# rauschsimulator_V4.net
KiCad netlist of a schematic drawn in EAGLE
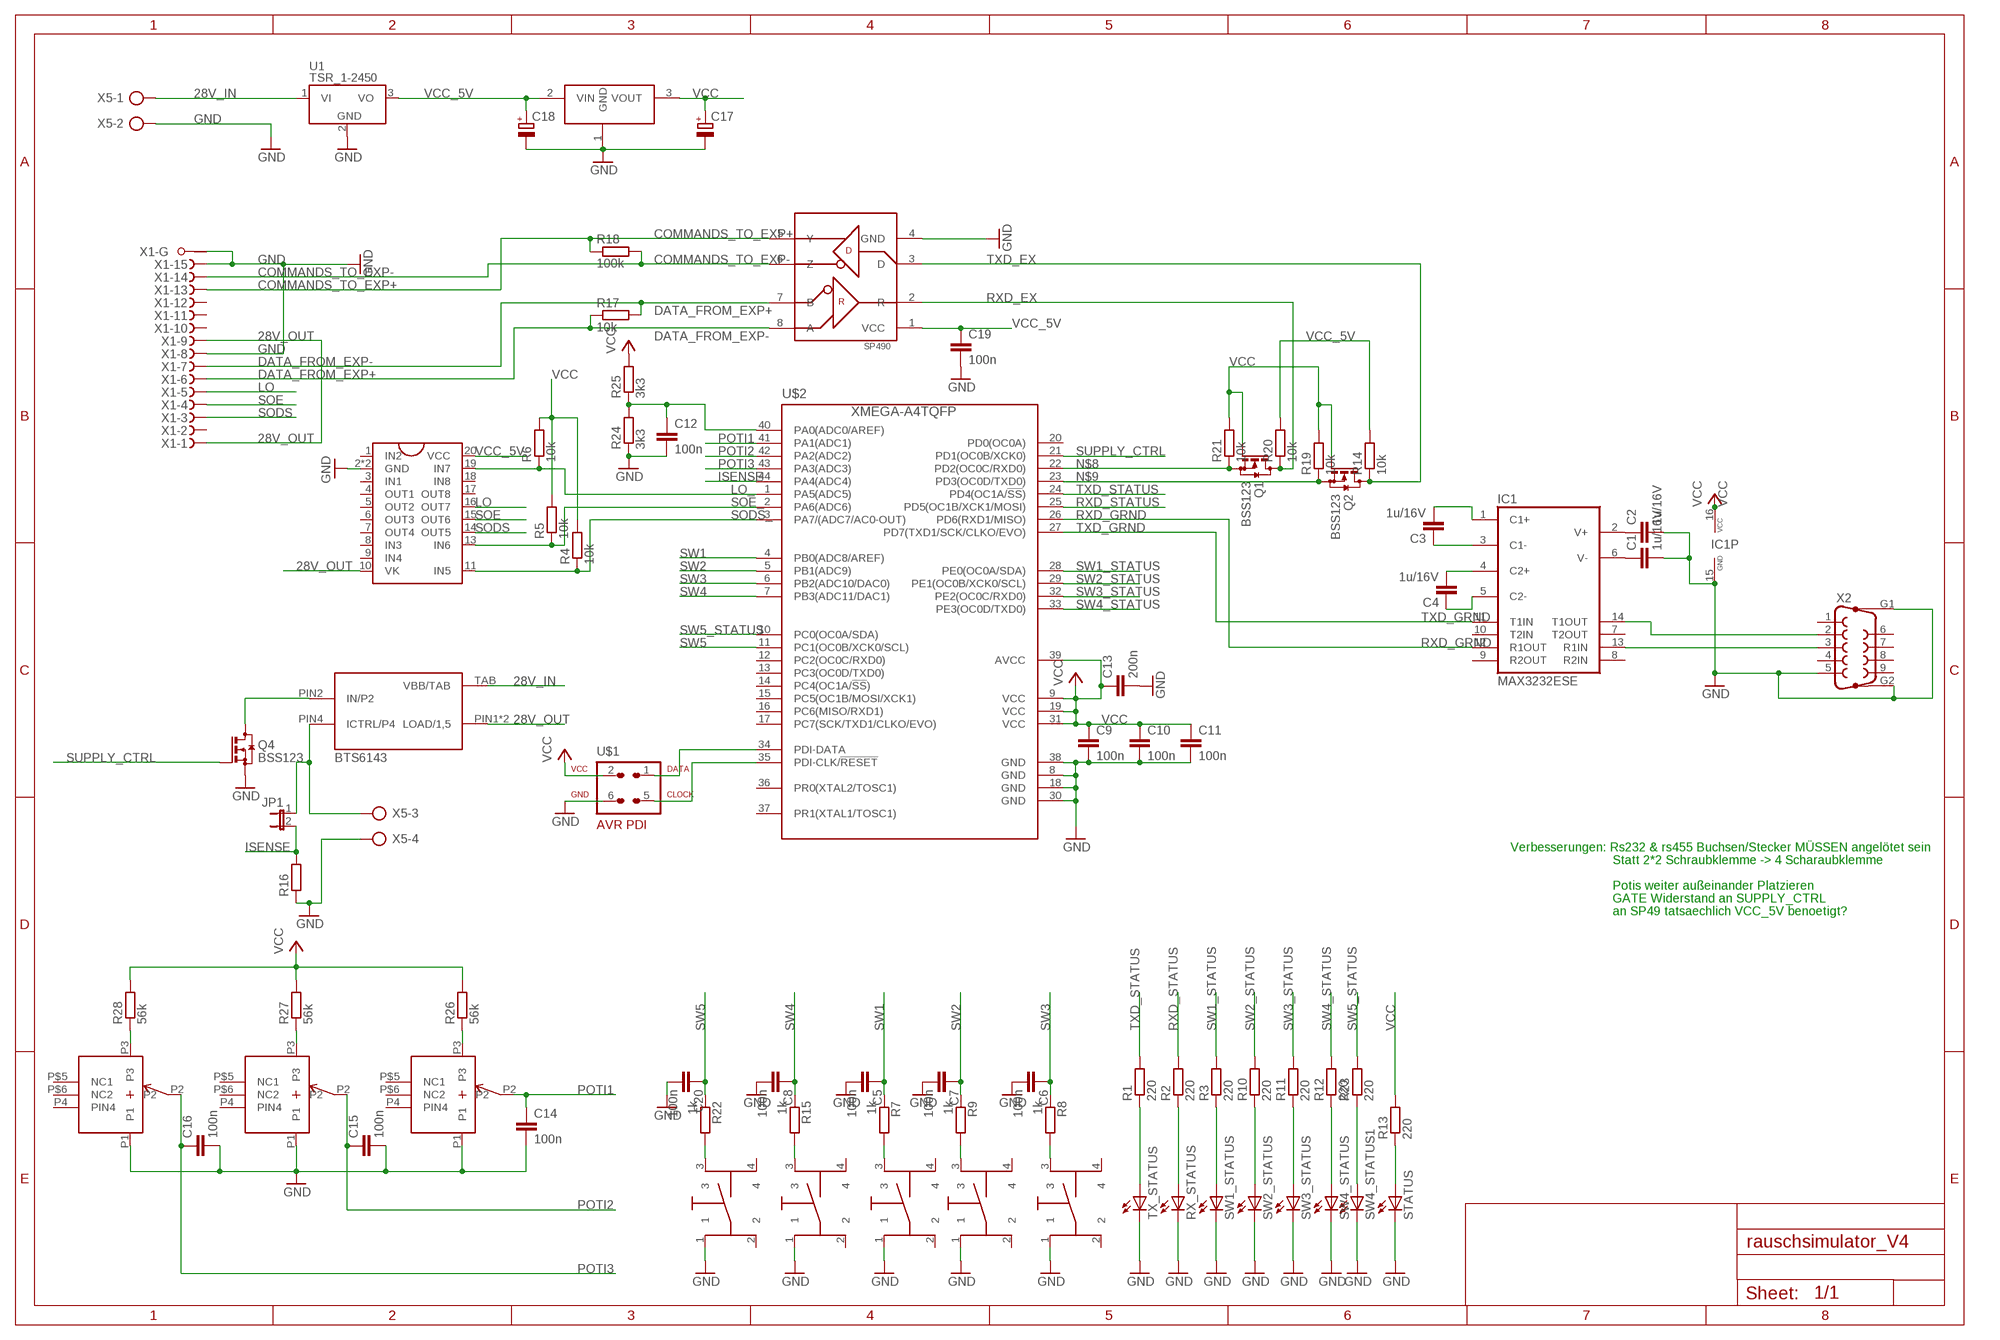
[diagram p0: schematic, sheet 1]

(export (version "E")
  (design (tool "Eeschema 10.0.6"))
  (components
    (comp (ref "C1")
      (value "1u/16V")
      (footprint "eagle-import:C0603K")
      (libsource (lib "eagle-import") (part "C-EUC0603K"))
    )
    (comp (ref "C2")
      (value "1u/16V")
      (footprint "eagle-import:C0603K")
      (libsource (lib "eagle-import") (part "C-EUC0603K"))
    )
    (comp (ref "C3")
      (value "1u/16V")
      (footprint "eagle-import:C0603K")
      (libsource (lib "eagle-import") (part "C-EUC0603K"))
    )
    (comp (ref "C4")
      (value "1u/16V")
      (footprint "eagle-import:C0603K")
      (libsource (lib "eagle-import") (part "C-EUC0603K"))
    )
    (comp (ref "C5")
      (value "100n")
      (footprint "eagle-import:C0603K")
      (libsource (lib "eagle-import") (part "C-EUC0603K"))
    )
    (comp (ref "C6")
      (value "100n")
      (footprint "eagle-import:C0603K")
      (libsource (lib "eagle-import") (part "C-EUC0603K"))
    )
    (comp (ref "C7")
      (value "100n")
      (footprint "eagle-import:C0603K")
      (libsource (lib "eagle-import") (part "C-EUC0603K"))
    )
    (comp (ref "C8")
      (value "100n")
      (footprint "eagle-import:C0603K")
      (libsource (lib "eagle-import") (part "C-EUC0603K"))
    )
    (comp (ref "C9")
      (value "100n")
      (footprint "eagle-import:C0603K")
      (libsource (lib "eagle-import") (part "C-EUC0603K"))
    )
    (comp (ref "C10")
      (value "100n")
      (footprint "eagle-import:C0603K")
      (libsource (lib "eagle-import") (part "C-EUC0603K"))
    )
    (comp (ref "C11")
      (value "100n")
      (footprint "eagle-import:C0603K")
      (libsource (lib "eagle-import") (part "C-EUC0603K"))
    )
    (comp (ref "C12")
      (value "100n")
      (footprint "eagle-import:C0603K")
      (libsource (lib "eagle-import") (part "C-EUC0603K"))
    )
    (comp (ref "C13")
      (value "200n")
      (footprint "eagle-import:C0603K")
      (libsource (lib "eagle-import") (part "C-EUC0603K"))
    )
    (comp (ref "C14")
      (value "100n")
      (footprint "eagle-import:C0603K")
      (libsource (lib "eagle-import") (part "C-EUC0603K"))
    )
    (comp (ref "C15")
      (value "100n")
      (footprint "eagle-import:C0603K")
      (libsource (lib "eagle-import") (part "C-EUC0603K"))
    )
    (comp (ref "C16")
      (value "100n")
      (footprint "eagle-import:C0603K")
      (libsource (lib "eagle-import") (part "C-EUC0603K"))
    )
    (comp (ref "C17")
      (value "CPOL-EUE2.5-6")
      (footprint "eagle-import:E2,5-6")
      (libsource (lib "eagle-import") (part "CPOL-EUE2.5-6"))
    )
    (comp (ref "C18")
      (value "CPOL-EUE2.5-6")
      (footprint "eagle-import:E2,5-6")
      (libsource (lib "eagle-import") (part "CPOL-EUE2.5-6"))
    )
    (comp (ref "C19")
      (value "100n")
      (footprint "eagle-import:C0603K")
      (libsource (lib "eagle-import") (part "C-EUC0603K"))
    )
    (comp (ref "C20")
      (value "100n")
      (footprint "eagle-import:C0603K")
      (libsource (lib "eagle-import") (part "C-EUC0603K"))
    )
    (comp (ref "IC1")
      (value "MAX3232ESE")
      (footprint "eagle-import:SO16")
      (fields (field (name "MF") "MAXIM"))
      (libsource (lib "eagle-import") (part "MAX3232SEE"))
    )
    (comp (ref "JP1")
      (value "JP1E")
      (footprint "eagle-import:JP1")
      (libsource (lib "eagle-import") (part "JP1E"))
    )
    (comp (ref "Q1")
      (value "BSS123")
      (footprint "eagle-import:SOT23")
      (libsource (lib "eagle-import") (part "BSS123"))
    )
    (comp (ref "Q2")
      (value "BSS123")
      (footprint "eagle-import:SOT23")
      (libsource (lib "eagle-import") (part "BSS123"))
    )
    (comp (ref "Q4")
      (value "BSS123")
      (footprint "eagle-import:SOT23")
      (libsource (lib "eagle-import") (part "BSS123"))
    )
    (comp (ref "R1")
      (value "220")
      (footprint "eagle-import:R0603")
      (libsource (lib "eagle-import") (part "R-EU_R0603"))
    )
    (comp (ref "R2")
      (value "220")
      (footprint "eagle-import:R0603")
      (libsource (lib "eagle-import") (part "R-EU_R0603"))
    )
    (comp (ref "R3")
      (value "220")
      (footprint "eagle-import:R0603")
      (libsource (lib "eagle-import") (part "R-EU_R0603"))
    )
    (comp (ref "R4")
      (value "10k")
      (footprint "eagle-import:R0603")
      (libsource (lib "eagle-import") (part "R-EU_R0603"))
    )
    (comp (ref "R5")
      (value "10k")
      (footprint "eagle-import:R0603")
      (libsource (lib "eagle-import") (part "R-EU_R0603"))
    )
    (comp (ref "R6")
      (value "10k")
      (footprint "eagle-import:R0603")
      (libsource (lib "eagle-import") (part "R-EU_R0603"))
    )
    (comp (ref "R7")
      (value "1k")
      (footprint "eagle-import:R0603")
      (libsource (lib "eagle-import") (part "R-EU_R0603"))
    )
    (comp (ref "R8")
      (value "1k")
      (footprint "eagle-import:R0603")
      (libsource (lib "eagle-import") (part "R-EU_R0603"))
    )
    (comp (ref "R9")
      (value "1k")
      (footprint "eagle-import:R0603")
      (libsource (lib "eagle-import") (part "R-EU_R0603"))
    )
    (comp (ref "R10")
      (value "220")
      (footprint "eagle-import:R0603")
      (libsource (lib "eagle-import") (part "R-EU_R0603"))
    )
    (comp (ref "R11")
      (value "220")
      (footprint "eagle-import:R0603")
      (libsource (lib "eagle-import") (part "R-EU_R0603"))
    )
    (comp (ref "R12")
      (value "220")
      (footprint "eagle-import:R0603")
      (libsource (lib "eagle-import") (part "R-EU_R0603"))
    )
    (comp (ref "R13")
      (value "220")
      (footprint "eagle-import:R0603")
      (libsource (lib "eagle-import") (part "R-EU_R0603"))
    )
    (comp (ref "R14")
      (value "10k")
      (footprint "eagle-import:R0603")
      (libsource (lib "eagle-import") (part "R-EU_R0603"))
    )
    (comp (ref "R15")
      (value "1k")
      (footprint "eagle-import:R0603")
      (libsource (lib "eagle-import") (part "R-EU_R0603"))
    )
    (comp (ref "R16")
      (value "R-EU_0617/22")
      (footprint "eagle-import:0617_22")
      (libsource (lib "eagle-import") (part "R-EU_0617/22"))
    )
    (comp (ref "R17")
      (value "10k")
      (footprint "eagle-import:R0603")
      (libsource (lib "eagle-import") (part "R-EU_R0603"))
    )
    (comp (ref "R18")
      (value "100k")
      (footprint "eagle-import:R0603")
      (libsource (lib "eagle-import") (part "R-EU_R0603"))
    )
    (comp (ref "R19")
      (value "10k")
      (footprint "eagle-import:R0603")
      (libsource (lib "eagle-import") (part "R-EU_R0603"))
    )
    (comp (ref "R20")
      (value "10k")
      (footprint "eagle-import:R0603")
      (libsource (lib "eagle-import") (part "R-EU_R0603"))
    )
    (comp (ref "R21")
      (value "10k")
      (footprint "eagle-import:R0603")
      (libsource (lib "eagle-import") (part "R-EU_R0603"))
    )
    (comp (ref "R22")
      (value "1k")
      (footprint "eagle-import:R0603")
      (libsource (lib "eagle-import") (part "R-EU_R0603"))
    )
    (comp (ref "R23")
      (value "220")
      (footprint "eagle-import:R0603")
      (libsource (lib "eagle-import") (part "R-EU_R0603"))
    )
    (comp (ref "R24")
      (value "3k3")
      (footprint "eagle-import:R0603")
      (libsource (lib "eagle-import") (part "R-EU_R0603"))
    )
    (comp (ref "R25")
      (value "3k3")
      (footprint "eagle-import:R0603")
      (libsource (lib "eagle-import") (part "R-EU_R0603"))
    )
    (comp (ref "R26")
      (value "56k")
      (footprint "eagle-import:R0603")
      (libsource (lib "eagle-import") (part "R-EU_R0603"))
    )
    (comp (ref "R27")
      (value "56k")
      (footprint "eagle-import:R0603")
      (libsource (lib "eagle-import") (part "R-EU_R0603"))
    )
    (comp (ref "R28")
      (value "56k")
      (footprint "eagle-import:R0603")
      (libsource (lib "eagle-import") (part "R-EU_R0603"))
    )
    (comp (ref "RX_STATUS")
      (value "LEDCHIPLED_1206")
      (footprint "eagle-import:CHIPLED_1206")
      (libsource (lib "eagle-import") (part "LEDCHIPLED_1206"))
    )
    (comp (ref "STATUS")
      (value "LEDCHIPLED_1206")
      (footprint "eagle-import:CHIPLED_1206")
      (libsource (lib "eagle-import") (part "LEDCHIPLED_1206"))
    )
    (comp (ref "SW1")
      (value "SMS_IP67")
      (footprint "eagle-import:IP67")
      (libsource (lib "eagle-import") (part "SMS_IP67"))
    )
    (comp (ref "SW1_STATUS")
      (value "LEDCHIPLED_1206")
      (footprint "eagle-import:CHIPLED_1206")
      (libsource (lib "eagle-import") (part "LEDCHIPLED_1206"))
    )
    (comp (ref "SW2")
      (value "SMS_IP67")
      (footprint "eagle-import:IP67")
      (libsource (lib "eagle-import") (part "SMS_IP67"))
    )
    (comp (ref "SW2_STATUS")
      (value "LEDCHIPLED_1206")
      (footprint "eagle-import:CHIPLED_1206")
      (libsource (lib "eagle-import") (part "LEDCHIPLED_1206"))
    )
    (comp (ref "SW3")
      (value "SMS_IP67")
      (footprint "eagle-import:IP67")
      (libsource (lib "eagle-import") (part "SMS_IP67"))
    )
    (comp (ref "SW3_STATUS")
      (value "LEDCHIPLED_1206")
      (footprint "eagle-import:CHIPLED_1206")
      (libsource (lib "eagle-import") (part "LEDCHIPLED_1206"))
    )
    (comp (ref "SW4")
      (value "SMS_IP67")
      (footprint "eagle-import:IP67")
      (libsource (lib "eagle-import") (part "SMS_IP67"))
    )
    (comp (ref "SW4_STATUS")
      (value "LEDCHIPLED_1206")
      (footprint "eagle-import:CHIPLED_1206")
      (libsource (lib "eagle-import") (part "LEDCHIPLED_1206"))
    )
    (comp (ref "SW4_STATUS1")
      (value "LEDCHIPLED_1206")
      (footprint "eagle-import:CHIPLED_1206")
      (libsource (lib "eagle-import") (part "LEDCHIPLED_1206"))
    )
    (comp (ref "SW5")
      (value "SMS_IP67")
      (footprint "eagle-import:IP67")
      (libsource (lib "eagle-import") (part "SMS_IP67"))
    )
    (comp (ref "TX_STATUS")
      (value "LEDCHIPLED_1206")
      (footprint "eagle-import:CHIPLED_1206")
      (libsource (lib "eagle-import") (part "LEDCHIPLED_1206"))
    )
    (comp (ref "U$1")
      (value "AVR-PDIVERT")
      (footprint "eagle-import:AVR-ISP-6")
      (libsource (lib "eagle-import") (part "AVR-PDIVERT"))
    )
    (comp (ref "U$2")
      (value "XMEGA-A4TQFP")
      (footprint "eagle-import:TQFP44")
      (libsource (lib "eagle-import") (part "XMEGA-A4TQFP"))
    )
    (comp (ref "U$3")
      (value "STRK11K")
      (footprint "eagle-import:VERT_POTI")
      (libsource (lib "eagle-import") (part "STRK11K"))
    )
    (comp (ref "U$4")
      (value "STRK11K")
      (footprint "eagle-import:VERT_POTI")
      (libsource (lib "eagle-import") (part "STRK11K"))
    )
    (comp (ref "U$5")
      (value "STRK11K")
      (footprint "eagle-import:VERT_POTI")
      (libsource (lib "eagle-import") (part "STRK11K"))
    )
    (comp (ref "U$13")
      (value "LM1117")
      (footprint "eagle-import:TO252")
      (libsource (lib "eagle-import") (part "LM1117"))
    )
    (comp (ref "U$14")
      (value "BTS6143")
      (footprint "eagle-import:TO-252-5-1")
      (libsource (lib "eagle-import") (part "BTS6143"))
    )
    (comp (ref "U$15")
      (value "UDN2596")
      (footprint "eagle-import:DIL20")
      (libsource (lib "eagle-import") (part "UDN2596"))
    )
    (comp (ref "U$16")
      (value "SP490")
      (footprint "eagle-import:SO08")
      (libsource (lib "eagle-import") (part "SP490"))
    )
    (comp (ref "U1")
      (value "TSR_1-2450")
      (footprint "eagle-import:TSR-1")
      (libsource (lib "eagle-import") (part "TSR_1-2450"))
    )
    (comp (ref "X1")
      (value "F15HPS")
      (footprint "eagle-import:F15HP")
      (libsource (lib "eagle-import") (part "F15HPS"))
    )
    (comp (ref "X2")
      (value "F09HP")
      (footprint "eagle-import:F09HP")
      (libsource (lib "eagle-import") (part "F09HP"))
    )
    (comp (ref "X5")
      (value "AK500/4")
      (footprint "eagle-import:AK500_4")
      (libsource (lib "eagle-import") (part "AK500/4"))
    )
  )
  (nets
    (net (code "1") (name "/28V_IN") (class "Default")
      (node (ref "U$14") (pin "TAB") (pinfunction "VBB/TAB_TAB") (pintype "bidirectional"))
      (node (ref "U1") (pin "1") (pinfunction "VI_1") (pintype "power_in"))
      (node (ref "X5") (pin "1") (pinfunction "KL_1") (pintype "passive"))
    )
    (net (code "2") (name "/28V_OUT") (class "Default")
      (node (ref "U$14") (pin "PIN1") (pinfunction "LOAD/1,5_PIN1") (pintype "bidirectional"))
      (node (ref "U$14") (pin "PIN5") (pinfunction "LOAD/1,5_PIN5") (pintype "bidirectional"))
      (node (ref "U$15") (pin "10") (pinfunction "VK_10") (pintype "bidirectional"))
      (node (ref "X1") (pin "1") (pinfunction "F_1") (pintype "passive"))
      (node (ref "X1") (pin "9") (pinfunction "F_9") (pintype "passive"))
    )
    (net (code "3") (name "/COMMANDS_TO_EXP+") (class "Default")
      (node (ref "R18") (pin "1") (pinfunction "1_1") (pintype "passive"))
      (node (ref "U$16") (pin "5") (pinfunction "Y_5") (pintype "bidirectional"))
      (node (ref "X1") (pin "13") (pinfunction "F_13") (pintype "passive"))
    )
    (net (code "4") (name "/COMMANDS_TO_EXP-") (class "Default")
      (node (ref "R18") (pin "2") (pinfunction "2_2") (pintype "passive"))
      (node (ref "U$16") (pin "6") (pinfunction "Z_6") (pintype "bidirectional"))
      (node (ref "X1") (pin "14") (pinfunction "F_14") (pintype "passive"))
    )
    (net (code "5") (name "/DATA_FROM_EXP+") (class "Default")
      (node (ref "R17") (pin "1") (pinfunction "1_1") (pintype "passive"))
      (node (ref "U$16") (pin "8") (pinfunction "A_8") (pintype "bidirectional"))
      (node (ref "X1") (pin "6") (pinfunction "F_6") (pintype "passive"))
    )
    (net (code "6") (name "/DATA_FROM_EXP-") (class "Default")
      (node (ref "R17") (pin "2") (pinfunction "2_2") (pintype "passive"))
      (node (ref "U$16") (pin "7") (pinfunction "B_7") (pintype "bidirectional"))
      (node (ref "X1") (pin "7") (pinfunction "F_7") (pintype "passive"))
    )
    (net (code "7") (name "/ISENSE") (class "Default")
      (node (ref "JP1") (pin "2") (pinfunction "2_2") (pintype "passive"))
      (node (ref "R16") (pin "2") (pinfunction "2_2") (pintype "passive"))
      (node (ref "U$2") (pin "44") (pinfunction "PA4(ADC4)_44") (pintype "bidirectional"))
    )
    (net (code "8") (name "/LO") (class "Default")
      (node (ref "U$15") (pin "16") (pinfunction "OUT7_16") (pintype "bidirectional"))
      (node (ref "X1") (pin "5") (pinfunction "F_5") (pintype "passive"))
    )
    (net (code "9") (name "/LO_") (class "Default")
      (node (ref "R6") (pin "1") (pinfunction "1_1") (pintype "passive"))
      (node (ref "U$15") (pin "19") (pinfunction "IN7_19") (pintype "bidirectional"))
      (node (ref "U$2") (pin "1") (pinfunction "PA5(ADC5)_1") (pintype "bidirectional"))
    )
    (net (code "10") (name "/N$8") (class "Default")
      (node (ref "Q1") (pin "2") (pinfunction "S_2") (pintype "passive"))
      (node (ref "R21") (pin "1") (pinfunction "1_1") (pintype "passive"))
      (node (ref "U$2") (pin "22") (pinfunction "PD2(OC0C/RXD0)_22") (pintype "bidirectional"))
    )
    (net (code "11") (name "/N$9") (class "Default")
      (node (ref "Q2") (pin "2") (pinfunction "S_2") (pintype "passive"))
      (node (ref "R19") (pin "1") (pinfunction "1_1") (pintype "passive"))
      (node (ref "U$2") (pin "23") (pinfunction "PD3(OC0D/TXD0)_23") (pintype "bidirectional"))
    )
    (net (code "12") (name "/POTI1") (class "Default")
      (node (ref "C14") (pin "1") (pinfunction "1_1") (pintype "passive"))
      (node (ref "U$2") (pin "41") (pinfunction "PA1(ADC1)_41") (pintype "bidirectional"))
      (node (ref "U$5") (pin "P2") (pinfunction "P2_P2") (pintype "bidirectional"))
    )
    (net (code "13") (name "/POTI2") (class "Default")
      (node (ref "C15") (pin "1") (pinfunction "1_1") (pintype "passive"))
      (node (ref "U$2") (pin "42") (pinfunction "PA2(ADC2)_42") (pintype "bidirectional"))
      (node (ref "U$4") (pin "P2") (pinfunction "P2_P2") (pintype "bidirectional"))
    )
    (net (code "14") (name "/POTI3") (class "Default")
      (node (ref "C16") (pin "1") (pinfunction "1_1") (pintype "passive"))
      (node (ref "U$2") (pin "43") (pinfunction "PA3(ADC3)_43") (pintype "bidirectional"))
      (node (ref "U$3") (pin "P2") (pinfunction "P2_P2") (pintype "bidirectional"))
    )
    (net (code "15") (name "/RXD_EX") (class "Default")
      (node (ref "Q1") (pin "3") (pinfunction "D_3") (pintype "passive"))
      (node (ref "R20") (pin "1") (pinfunction "1_1") (pintype "passive"))
      (node (ref "U$16") (pin "2") (pinfunction "R_2") (pintype "bidirectional"))
    )
    (net (code "16") (name "/RXD_GRND") (class "Default")
      (node (ref "IC1") (pin "12") (pinfunction "R1OUT_12") (pintype "output"))
      (node (ref "U$2") (pin "26") (pinfunction "PD6(RXD1/MISO)_26") (pintype "bidirectional"))
    )
    (net (code "17") (name "/RXD_STATUS") (class "Default")
      (node (ref "R2") (pin "2") (pinfunction "2_2") (pintype "passive"))
      (node (ref "U$2") (pin "25") (pinfunction "PD5(OC1B/XCK1/MOSI)_25") (pintype "bidirectional"))
    )
    (net (code "18") (name "/SODS") (class "Default")
      (node (ref "U$15") (pin "14") (pinfunction "OUT5_14") (pintype "bidirectional"))
      (node (ref "X1") (pin "3") (pinfunction "F_3") (pintype "passive"))
    )
    (net (code "19") (name "/SODS_") (class "Default")
      (node (ref "R4") (pin "1") (pinfunction "1_1") (pintype "passive"))
      (node (ref "U$15") (pin "11") (pinfunction "IN5_11") (pintype "bidirectional"))
      (node (ref "U$2") (pin "3") (pinfunction "PA7/(ADC7/AC0-OUT)_3") (pintype "bidirectional"))
    )
    (net (code "20") (name "/SOE") (class "Default")
      (node (ref "U$15") (pin "15") (pinfunction "OUT6_15") (pintype "bidirectional"))
      (node (ref "X1") (pin "4") (pinfunction "F_4") (pintype "passive"))
    )
    (net (code "21") (name "/SOE_") (class "Default")
      (node (ref "R5") (pin "1") (pinfunction "1_1") (pintype "passive"))
      (node (ref "U$15") (pin "13") (pinfunction "IN6_13") (pintype "bidirectional"))
      (node (ref "U$2") (pin "2") (pinfunction "PA6(ADC6)_2") (pintype "bidirectional"))
    )
    (net (code "22") (name "/SUPPLY_CTRL") (class "Default")
      (node (ref "Q4") (pin "1") (pinfunction "G_1") (pintype "passive"))
      (node (ref "U$2") (pin "21") (pinfunction "PD1(OC0B/XCK0)_21") (pintype "bidirectional"))
    )
    (net (code "23") (name "/SW1") (class "Default")
      (node (ref "C5") (pin "1") (pinfunction "1_1") (pintype "passive"))
      (node (ref "R7") (pin "1") (pinfunction "1_1") (pintype "passive"))
      (node (ref "U$2") (pin "4") (pinfunction "PB0(ADC8/AREF)_4") (pintype "bidirectional"))
    )
    (net (code "24") (name "/SW1_STATUS") (class "Default")
      (node (ref "R3") (pin "2") (pinfunction "2_2") (pintype "passive"))
      (node (ref "U$2") (pin "28") (pinfunction "PE0(OC0A/SDA)_28") (pintype "bidirectional"))
    )
    (net (code "25") (name "/SW2") (class "Default")
      (node (ref "C7") (pin "1") (pinfunction "1_1") (pintype "passive"))
      (node (ref "R9") (pin "1") (pinfunction "1_1") (pintype "passive"))
      (node (ref "U$2") (pin "5") (pinfunction "PB1(ADC9)_5") (pintype "bidirectional"))
    )
    (net (code "26") (name "/SW2_STATUS") (class "Default")
      (node (ref "R10") (pin "2") (pinfunction "2_2") (pintype "passive"))
      (node (ref "U$2") (pin "29") (pinfunction "PE1(OC0B/XCK0/SCL)_29") (pintype "bidirectional"))
    )
    (net (code "27") (name "/SW3") (class "Default")
      (node (ref "C6") (pin "1") (pinfunction "1_1") (pintype "passive"))
      (node (ref "R8") (pin "1") (pinfunction "1_1") (pintype "passive"))
      (node (ref "U$2") (pin "6") (pinfunction "PB2(ADC10/DAC0)_6") (pintype "bidirectional"))
    )
    (net (code "28") (name "/SW3_STATUS") (class "Default")
      (node (ref "R11") (pin "2") (pinfunction "2_2") (pintype "passive"))
      (node (ref "U$2") (pin "32") (pinfunction "PE2(OC0C/RXD0)_32") (pintype "bidirectional"))
    )
    (net (code "29") (name "/SW4") (class "Default")
      (node (ref "C8") (pin "1") (pinfunction "1_1") (pintype "passive"))
      (node (ref "R15") (pin "1") (pinfunction "1_1") (pintype "passive"))
      (node (ref "U$2") (pin "7") (pinfunction "PB3(ADC11/DAC1)_7") (pintype "bidirectional"))
    )
    (net (code "30") (name "/SW4_STATUS") (class "Default")
      (node (ref "R12") (pin "2") (pinfunction "2_2") (pintype "passive"))
      (node (ref "U$2") (pin "33") (pinfunction "PE3(OC0D/TXD0)_33") (pintype "bidirectional"))
    )
    (net (code "31") (name "/SW5") (class "Default")
      (node (ref "C20") (pin "1") (pinfunction "1_1") (pintype "passive"))
      (node (ref "R22") (pin "1") (pinfunction "1_1") (pintype "passive"))
      (node (ref "U$2") (pin "11") (pinfunction "PC1(OC0B/XCK0/SCL)_11") (pintype "bidirectional"))
    )
    (net (code "32") (name "/SW5_STATUS") (class "Default")
      (node (ref "R23") (pin "2") (pinfunction "2_2") (pintype "passive"))
      (node (ref "U$2") (pin "10") (pinfunction "PC0(OC0A/SDA)_10") (pintype "bidirectional"))
    )
    (net (code "33") (name "/TXD_EX") (class "Default")
      (node (ref "Q2") (pin "3") (pinfunction "D_3") (pintype "passive"))
      (node (ref "R14") (pin "1") (pinfunction "1_1") (pintype "passive"))
      (node (ref "U$16") (pin "3") (pinfunction "D_3") (pintype "bidirectional"))
    )
    (net (code "34") (name "/TXD_GRND") (class "Default")
      (node (ref "IC1") (pin "11") (pinfunction "T1IN_11") (pintype "input"))
      (node (ref "U$2") (pin "27") (pinfunction "PD7(TXD1/SCK/CLKO/EVO)_27") (pintype "bidirectional"))
    )
    (net (code "35") (name "/TXD_STATUS") (class "Default")
      (node (ref "R1") (pin "2") (pinfunction "2_2") (pintype "passive"))
      (node (ref "U$2") (pin "24") (pinfunction "PD4(OC1A/~{SS})_24") (pintype "bidirectional"))
    )
    (net (code "36") (name "/VCC_5V") (class "Default")
      (node (ref "C18") (pin "+") (pinfunction "+_+") (pintype "passive"))
      (node (ref "C19") (pin "1") (pinfunction "1_1") (pintype "passive"))
      (node (ref "R14") (pin "2") (pinfunction "2_2") (pintype "passive"))
      (node (ref "R20") (pin "2") (pinfunction "2_2") (pintype "passive"))
      (node (ref "U$13") (pin "2") (pinfunction "VIN_2") (pintype "bidirectional"))
      (node (ref "U$15") (pin "20") (pinfunction "VCC_20") (pintype "bidirectional"))
      (node (ref "U$16") (pin "1") (pinfunction "VCC_1") (pintype "bidirectional"))
      (node (ref "U1") (pin "3") (pinfunction "VO_3") (pintype "power_in"))
    )
    (net (code "37") (name "GND") (class "Default")
      (node (ref "C1") (pin "2") (pinfunction "2_2") (pintype "passive"))
      (node (ref "C10") (pin "2") (pinfunction "2_2") (pintype "passive"))
      (node (ref "C11") (pin "2") (pinfunction "2_2") (pintype "passive"))
      (node (ref "C12") (pin "2") (pinfunction "2_2") (pintype "passive"))
      (node (ref "C13") (pin "2") (pinfunction "2_2") (pintype "passive"))
      (node (ref "C14") (pin "2") (pinfunction "2_2") (pintype "passive"))
      (node (ref "C15") (pin "2") (pinfunction "2_2") (pintype "passive"))
      (node (ref "C16") (pin "2") (pinfunction "2_2") (pintype "passive"))
      (node (ref "C17") (pin "-") (pinfunction "-_-") (pintype "passive"))
      (node (ref "C18") (pin "-") (pinfunction "-_-") (pintype "passive"))
      (node (ref "C19") (pin "2") (pinfunction "2_2") (pintype "passive"))
      (node (ref "C2") (pin "2") (pinfunction "2_2") (pintype "passive"))
      (node (ref "C20") (pin "2") (pinfunction "2_2") (pintype "passive"))
      (node (ref "C5") (pin "2") (pinfunction "2_2") (pintype "passive"))
      (node (ref "C6") (pin "2") (pinfunction "2_2") (pintype "passive"))
      (node (ref "C7") (pin "2") (pinfunction "2_2") (pintype "passive"))
      (node (ref "C8") (pin "2") (pinfunction "2_2") (pintype "passive"))
      (node (ref "C9") (pin "2") (pinfunction "2_2") (pintype "passive"))
      (node (ref "IC1") (pin "15") (pinfunction "GND_15") (pintype "power_in"))
      (node (ref "Q4") (pin "2") (pinfunction "S_2") (pintype "passive"))
      (node (ref "R16") (pin "1") (pinfunction "1_1") (pintype "passive"))
      (node (ref "R24") (pin "1") (pinfunction "1_1") (pintype "passive"))
      (node (ref "RX_STATUS") (pin "C") (pinfunction "C_C") (pintype "passive"))
      (node (ref "STATUS") (pin "C") (pinfunction "C_C") (pintype "passive"))
      (node (ref "SW1") (pin "1") (pinfunction "1_1") (pintype "bidirectional"))
      (node (ref "SW1_STATUS") (pin "C") (pinfunction "C_C") (pintype "passive"))
      (node (ref "SW2") (pin "1") (pinfunction "1_1") (pintype "bidirectional"))
      (node (ref "SW2_STATUS") (pin "C") (pinfunction "C_C") (pintype "passive"))
      (node (ref "SW3") (pin "1") (pinfunction "1_1") (pintype "bidirectional"))
      (node (ref "SW3_STATUS") (pin "C") (pinfunction "C_C") (pintype "passive"))
      (node (ref "SW4") (pin "1") (pinfunction "1_1") (pintype "bidirectional"))
      (node (ref "SW4_STATUS") (pin "C") (pinfunction "C_C") (pintype "passive"))
      (node (ref "SW4_STATUS1") (pin "C") (pinfunction "C_C") (pintype "passive"))
      (node (ref "SW5") (pin "1") (pinfunction "1_1") (pintype "bidirectional"))
      (node (ref "TX_STATUS") (pin "C") (pinfunction "C_C") (pintype "passive"))
      (node (ref "U$1") (pin "6") (pinfunction "6_6") (pintype "passive"))
      (node (ref "U$13") (pin "1") (pinfunction "GND_1") (pintype "bidirectional"))
      (node (ref "U$15") (pin "12") (pinfunction "GND_12") (pintype "bidirectional"))
      (node (ref "U$15") (pin "2") (pinfunction "GND_2") (pintype "bidirectional"))
      (node (ref "U$16") (pin "4") (pinfunction "GND_4") (pintype "bidirectional"))
      (node (ref "U$2") (pin "18") (pinfunction "GND_18") (pintype "power_in"))
      (node (ref "U$2") (pin "30") (pinfunction "GND_30") (pintype "power_in"))
      (node (ref "U$2") (pin "38") (pinfunction "GND_38") (pintype "power_in"))
      (node (ref "U$2") (pin "8") (pinfunction "GND_8") (pintype "power_in"))
      (node (ref "U$3") (pin "P1") (pinfunction "P1_P1") (pintype "bidirectional"))
      (node (ref "U$4") (pin "P1") (pinfunction "P1_P1") (pintype "bidirectional"))
      (node (ref "U$5") (pin "P1") (pinfunction "P1_P1") (pintype "bidirectional"))
      (node (ref "U1") (pin "2") (pinfunction "GND_2") (pintype "power_in"))
      (node (ref "X1") (pin "15") (pinfunction "F_15") (pintype "passive"))
      (node (ref "X1") (pin "8") (pinfunction "F_8") (pintype "passive"))
      (node (ref "X1") (pin "G1") (pinfunction "G1_G1") (pintype "passive"))
      (node (ref "X2") (pin "5") (pinfunction "5_5") (pintype "passive"))
      (node (ref "X2") (pin "G1") (pinfunction "G1_G1") (pintype "passive"))
      (node (ref "X2") (pin "G2") (pinfunction "G2_G2") (pintype "passive"))
      (node (ref "X5") (pin "2") (pinfunction "KL_2") (pintype "passive"))
      (node (ref "X5") (pin "4") (pinfunction "KL_4") (pintype "passive"))
    )
    (net (code "38") (name "Net-(IC1A-C1+)") (class "Default")
      (node (ref "C3") (pin "2") (pinfunction "2_2") (pintype "passive"))
      (node (ref "IC1") (pin "1") (pinfunction "C1+_1") (pintype "bidirectional"))
    )
    (net (code "39") (name "Net-(IC1A-C1-)") (class "Default")
      (node (ref "C3") (pin "1") (pinfunction "1_1") (pintype "passive"))
      (node (ref "IC1") (pin "3") (pinfunction "C1-_3") (pintype "bidirectional"))
    )
    (net (code "40") (name "Net-(IC1A-C2+)") (class "Default")
      (node (ref "C4") (pin "2") (pinfunction "2_2") (pintype "passive"))
      (node (ref "IC1") (pin "4") (pinfunction "C2+_4") (pintype "bidirectional"))
    )
    (net (code "41") (name "Net-(IC1A-C2-)") (class "Default")
      (node (ref "C4") (pin "1") (pinfunction "1_1") (pintype "passive"))
      (node (ref "IC1") (pin "5") (pinfunction "C2-_5") (pintype "bidirectional"))
    )
    (net (code "42") (name "Net-(IC1A-R1IN)") (class "Default")
      (node (ref "IC1") (pin "13") (pinfunction "R1IN_13") (pintype "input"))
      (node (ref "X2") (pin "3") (pinfunction "3_3") (pintype "passive"))
    )
    (net (code "43") (name "Net-(IC1A-T1OUT)") (class "Default")
      (node (ref "IC1") (pin "14") (pinfunction "T1OUT_14") (pintype "output"))
      (node (ref "X2") (pin "2") (pinfunction "2_2") (pintype "passive"))
    )
    (net (code "44") (name "Net-(IC1A-V+)") (class "Default")
      (node (ref "C2") (pin "1") (pinfunction "1_1") (pintype "passive"))
      (node (ref "IC1") (pin "2") (pinfunction "V+_2") (pintype "bidirectional"))
    )
    (net (code "45") (name "Net-(IC1A-V-)") (class "Default")
      (node (ref "C1") (pin "1") (pinfunction "1_1") (pintype "passive"))
      (node (ref "IC1") (pin "6") (pinfunction "V-_6") (pintype "bidirectional"))
    )
    (net (code "46") (name "Net-(Q4-D)") (class "Default")
      (node (ref "Q4") (pin "3") (pinfunction "D_3") (pintype "passive"))
      (node (ref "U$14") (pin "PIN2") (pinfunction "IN/P2_PIN2") (pintype "bidirectional"))
    )
    (net (code "47") (name "Net-(R1-Pad1)") (class "Default")
      (node (ref "R1") (pin "1") (pinfunction "1_1") (pintype "passive"))
      (node (ref "TX_STATUS") (pin "A") (pinfunction "A_A") (pintype "passive"))
    )
    (net (code "48") (name "Net-(R2-Pad1)") (class "Default")
      (node (ref "R2") (pin "1") (pinfunction "1_1") (pintype "passive"))
      (node (ref "RX_STATUS") (pin "A") (pinfunction "A_A") (pintype "passive"))
    )
    (net (code "49") (name "Net-(R3-Pad1)") (class "Default")
      (node (ref "R3") (pin "1") (pinfunction "1_1") (pintype "passive"))
      (node (ref "SW1_STATUS") (pin "A") (pinfunction "A_A") (pintype "passive"))
    )
    (net (code "50") (name "Net-(R7-Pad2)") (class "Default")
      (node (ref "R7") (pin "2") (pinfunction "2_2") (pintype "passive"))
      (node (ref "SW3") (pin "3") (pinfunction "3_3") (pintype "bidirectional"))
    )
    (net (code "51") (name "Net-(R8-Pad2)") (class "Default")
      (node (ref "R8") (pin "2") (pinfunction "2_2") (pintype "passive"))
      (node (ref "SW1") (pin "3") (pinfunction "3_3") (pintype "bidirectional"))
    )
    (net (code "52") (name "Net-(R9-Pad2)") (class "Default")
      (node (ref "R9") (pin "2") (pinfunction "2_2") (pintype "passive"))
      (node (ref "SW2") (pin "3") (pinfunction "3_3") (pintype "bidirectional"))
    )
    (net (code "53") (name "Net-(R10-Pad1)") (class "Default")
      (node (ref "R10") (pin "1") (pinfunction "1_1") (pintype "passive"))
      (node (ref "SW2_STATUS") (pin "A") (pinfunction "A_A") (pintype "passive"))
    )
    (net (code "54") (name "Net-(R11-Pad1)") (class "Default")
      (node (ref "R11") (pin "1") (pinfunction "1_1") (pintype "passive"))
      (node (ref "SW3_STATUS") (pin "A") (pinfunction "A_A") (pintype "passive"))
    )
    (net (code "55") (name "Net-(R12-Pad1)") (class "Default")
      (node (ref "R12") (pin "1") (pinfunction "1_1") (pintype "passive"))
      (node (ref "SW4_STATUS") (pin "A") (pinfunction "A_A") (pintype "passive"))
    )
    (net (code "56") (name "Net-(R13-Pad1)") (class "Default")
      (node (ref "R13") (pin "1") (pinfunction "1_1") (pintype "passive"))
      (node (ref "STATUS") (pin "A") (pinfunction "A_A") (pintype "passive"))
    )
    (net (code "57") (name "Net-(R15-Pad2)") (class "Default")
      (node (ref "R15") (pin "2") (pinfunction "2_2") (pintype "passive"))
      (node (ref "SW4") (pin "3") (pinfunction "3_3") (pintype "bidirectional"))
    )
    (net (code "58") (name "Net-(R22-Pad2)") (class "Default")
      (node (ref "R22") (pin "2") (pinfunction "2_2") (pintype "passive"))
      (node (ref "SW5") (pin "3") (pinfunction "3_3") (pintype "bidirectional"))
    )
    (net (code "59") (name "Net-(R23-Pad1)") (class "Default")
      (node (ref "R23") (pin "1") (pinfunction "1_1") (pintype "passive"))
      (node (ref "SW4_STATUS1") (pin "A") (pinfunction "A_A") (pintype "passive"))
    )
    (net (code "60") (name "Net-(R26-Pad1)") (class "Default")
      (node (ref "R26") (pin "1") (pinfunction "1_1") (pintype "passive"))
      (node (ref "U$5") (pin "P3") (pinfunction "P3_P3") (pintype "bidirectional"))
    )
    (net (code "61") (name "Net-(R27-Pad1)") (class "Default")
      (node (ref "R27") (pin "1") (pinfunction "1_1") (pintype "passive"))
      (node (ref "U$4") (pin "P3") (pinfunction "P3_P3") (pintype "bidirectional"))
    )
    (net (code "62") (name "Net-(R28-Pad1)") (class "Default")
      (node (ref "R28") (pin "1") (pinfunction "1_1") (pintype "passive"))
      (node (ref "U$3") (pin "P3") (pinfunction "P3_P3") (pintype "bidirectional"))
    )
    (net (code "63") (name "Net-(U$2-PA0(ADC0{slash}AREF))") (class "Default")
      (node (ref "C12") (pin "1") (pinfunction "1_1") (pintype "passive"))
      (node (ref "R24") (pin "2") (pinfunction "2_2") (pintype "passive"))
      (node (ref "R25") (pin "1") (pinfunction "1_1") (pintype "passive"))
      (node (ref "U$2") (pin "40") (pinfunction "PA0(ADC0/AREF)_40") (pintype "bidirectional"))
    )
    (net (code "64") (name "Net-(U$2-PDI-CLK{slash}~{RESET})") (class "Default")
      (node (ref "U$1") (pin "5") (pinfunction "5_5") (pintype "passive"))
      (node (ref "U$2") (pin "35") (pinfunction "PDI-CLK/~{RESET}_35") (pintype "input"))
    )
    (net (code "65") (name "Net-(U$2-PDI-DATA)") (class "Default")
      (node (ref "U$1") (pin "1") (pinfunction "1_1") (pintype "passive"))
      (node (ref "U$2") (pin "34") (pinfunction "PDI-DATA_34") (pintype "bidirectional"))
    )
    (net (code "66") (name "Net-(U$14-ICTRL{slash}P4)") (class "Default")
      (node (ref "JP1") (pin "1") (pinfunction "1_1") (pintype "passive"))
      (node (ref "U$14") (pin "PIN4") (pinfunction "ICTRL/P4_PIN4") (pintype "bidirectional"))
      (node (ref "X5") (pin "3") (pinfunction "KL_3") (pintype "passive"))
    )
    (net (code "67") (name "VCC") (class "Default")
      (node (ref "C10") (pin "1") (pinfunction "1_1") (pintype "passive"))
      (node (ref "C11") (pin "1") (pinfunction "1_1") (pintype "passive"))
      (node (ref "C13") (pin "1") (pinfunction "1_1") (pintype "passive"))
      (node (ref "C17") (pin "+") (pinfunction "+_+") (pintype "passive"))
      (node (ref "C9") (pin "1") (pinfunction "1_1") (pintype "passive"))
      (node (ref "IC1") (pin "16") (pinfunction "VCC_16") (pintype "power_in"))
      (node (ref "Q1") (pin "1") (pinfunction "G_1") (pintype "passive"))
      (node (ref "Q2") (pin "1") (pinfunction "G_1") (pintype "passive"))
      (node (ref "R13") (pin "2") (pinfunction "2_2") (pintype "passive"))
      (node (ref "R19") (pin "2") (pinfunction "2_2") (pintype "passive"))
      (node (ref "R21") (pin "2") (pinfunction "2_2") (pintype "passive"))
      (node (ref "R25") (pin "2") (pinfunction "2_2") (pintype "passive"))
      (node (ref "R26") (pin "2") (pinfunction "2_2") (pintype "passive"))
      (node (ref "R27") (pin "2") (pinfunction "2_2") (pintype "passive"))
      (node (ref "R28") (pin "2") (pinfunction "2_2") (pintype "passive"))
      (node (ref "R4") (pin "2") (pinfunction "2_2") (pintype "passive"))
      (node (ref "R5") (pin "2") (pinfunction "2_2") (pintype "passive"))
      (node (ref "R6") (pin "2") (pinfunction "2_2") (pintype "passive"))
      (node (ref "U$1") (pin "2") (pinfunction "2_2") (pintype "passive"))
      (node (ref "U$13") (pin "3") (pinfunction "VOUT_3") (pintype "bidirectional"))
      (node (ref "U$2") (pin "19") (pinfunction "VCC_19") (pintype "power_in"))
      (node (ref "U$2") (pin "31") (pinfunction "VCC_31") (pintype "power_in"))
      (node (ref "U$2") (pin "39") (pinfunction "AVCC_39") (pintype "power_in"))
      (node (ref "U$2") (pin "9") (pinfunction "VCC_9") (pintype "power_in"))
    )
    (net (code "68") (name "unconnected-(IC1A-R2IN-Pad8)") (class "Default")
      (node (ref "IC1") (pin "8") (pinfunction "R2IN_8") (pintype "input"))
    )
    (net (code "69") (name "unconnected-(IC1A-R2OUT-Pad9)") (class "Default")
      (node (ref "IC1") (pin "9") (pinfunction "R2OUT_9") (pintype "output"))
    )
    (net (code "70") (name "unconnected-(IC1A-T2IN-Pad10)") (class "Default")
      (node (ref "IC1") (pin "10") (pinfunction "T2IN_10") (pintype "input"))
    )
    (net (code "71") (name "unconnected-(IC1A-T2OUT-Pad7)") (class "Default")
      (node (ref "IC1") (pin "7") (pinfunction "T2OUT_7") (pintype "output"))
    )
    (net (code "72") (name "unconnected-(SW1-Pad2)") (class "Default")
      (node (ref "SW1") (pin "2") (pinfunction "2_2") (pintype "bidirectional"))
    )
    (net (code "73") (name "unconnected-(SW1-Pad4)") (class "Default")
      (node (ref "SW1") (pin "4") (pinfunction "4_4") (pintype "bidirectional"))
    )
    (net (code "74") (name "unconnected-(SW2-Pad2)") (class "Default")
      (node (ref "SW2") (pin "2") (pinfunction "2_2") (pintype "bidirectional"))
    )
    (net (code "75") (name "unconnected-(SW2-Pad4)") (class "Default")
      (node (ref "SW2") (pin "4") (pinfunction "4_4") (pintype "bidirectional"))
    )
    (net (code "76") (name "unconnected-(SW3-Pad2)") (class "Default")
      (node (ref "SW3") (pin "2") (pinfunction "2_2") (pintype "bidirectional"))
    )
    (net (code "77") (name "unconnected-(SW3-Pad4)") (class "Default")
      (node (ref "SW3") (pin "4") (pinfunction "4_4") (pintype "bidirectional"))
    )
    (net (code "78") (name "unconnected-(SW4-Pad2)") (class "Default")
      (node (ref "SW4") (pin "2") (pinfunction "2_2") (pintype "bidirectional"))
    )
    (net (code "79") (name "unconnected-(SW4-Pad4)") (class "Default")
      (node (ref "SW4") (pin "4") (pinfunction "4_4") (pintype "bidirectional"))
    )
    (net (code "80") (name "unconnected-(SW5-Pad2)") (class "Default")
      (node (ref "SW5") (pin "2") (pinfunction "2_2") (pintype "bidirectional"))
    )
    (net (code "81") (name "unconnected-(SW5-Pad4)") (class "Default")
      (node (ref "SW5") (pin "4") (pinfunction "4_4") (pintype "bidirectional"))
    )
    (net (code "82") (name "unconnected-(U$2-PC2(OC0C{slash}RXD0)-Pad12)") (class "Default")
      (node (ref "U$2") (pin "12") (pinfunction "PC2(OC0C/RXD0)_12") (pintype "bidirectional"))
    )
    (net (code "83") (name "unconnected-(U$2-PC3(OC0D{slash}TXD0)-Pad13)") (class "Default")
      (node (ref "U$2") (pin "13") (pinfunction "PC3(OC0D/TXD0)_13") (pintype "bidirectional"))
    )
    (net (code "84") (name "unconnected-(U$2-PC4(OC1A{slash}~{SS})-Pad14)") (class "Default")
      (node (ref "U$2") (pin "14") (pinfunction "PC4(OC1A/~{SS})_14") (pintype "bidirectional"))
    )
    (net (code "85") (name "unconnected-(U$2-PC5(OC1B{slash}MOSI{slash}XCK1)-Pad15)") (class "Default")
      (node (ref "U$2") (pin "15") (pinfunction "PC5(OC1B/MOSI/XCK1)_15") (pintype "bidirectional"))
    )
    (net (code "86") (name "unconnected-(U$2-PC6(MISO{slash}RXD1)-Pad16)") (class "Default")
      (node (ref "U$2") (pin "16") (pinfunction "PC6(MISO/RXD1)_16") (pintype "bidirectional"))
    )
    (net (code "87") (name "unconnected-(U$2-PC7(SCK{slash}TXD1{slash}CLKO{slash}EVO)-Pad17)") (class "Default")
      (node (ref "U$2") (pin "17") (pinfunction "PC7(SCK/TXD1/CLKO/EVO)_17") (pintype "bidirectional"))
    )
    (net (code "88") (name "unconnected-(U$2-PD0(OC0A)-Pad20)") (class "Default")
      (node (ref "U$2") (pin "20") (pinfunction "PD0(OC0A)_20") (pintype "bidirectional"))
    )
    (net (code "89") (name "unconnected-(U$2-PR0(XTAL2{slash}TOSC1)-Pad36)") (class "Default")
      (node (ref "U$2") (pin "36") (pinfunction "PR0(XTAL2/TOSC1)_36") (pintype "bidirectional"))
    )
    (net (code "90") (name "unconnected-(U$2-PR1(XTAL1{slash}TOSC1)-Pad37)") (class "Default")
      (node (ref "U$2") (pin "37") (pinfunction "PR1(XTAL1/TOSC1)_37") (pintype "bidirectional"))
    )
    (net (code "91") (name "unconnected-(U$3-NC1-PadP$5)") (class "Default")
      (node (ref "U$3") (pin "P$5") (pinfunction "NC1_P$5") (pintype "bidirectional"))
    )
    (net (code "92") (name "unconnected-(U$3-NC2-PadP$6)") (class "Default")
      (node (ref "U$3") (pin "P$6") (pinfunction "NC2_P$6") (pintype "bidirectional"))
    )
    (net (code "93") (name "unconnected-(U$3-PIN4-PadP4)") (class "Default")
      (node (ref "U$3") (pin "P4") (pinfunction "PIN4_P4") (pintype "bidirectional"))
    )
    (net (code "94") (name "unconnected-(U$4-NC1-PadP$5)") (class "Default")
      (node (ref "U$4") (pin "P$5") (pinfunction "NC1_P$5") (pintype "bidirectional"))
    )
    (net (code "95") (name "unconnected-(U$4-NC2-PadP$6)") (class "Default")
      (node (ref "U$4") (pin "P$6") (pinfunction "NC2_P$6") (pintype "bidirectional"))
    )
    (net (code "96") (name "unconnected-(U$4-PIN4-PadP4)") (class "Default")
      (node (ref "U$4") (pin "P4") (pinfunction "PIN4_P4") (pintype "bidirectional"))
    )
    (net (code "97") (name "unconnected-(U$5-NC1-PadP$5)") (class "Default")
      (node (ref "U$5") (pin "P$5") (pinfunction "NC1_P$5") (pintype "bidirectional"))
    )
    (net (code "98") (name "unconnected-(U$5-NC2-PadP$6)") (class "Default")
      (node (ref "U$5") (pin "P$6") (pinfunction "NC2_P$6") (pintype "bidirectional"))
    )
    (net (code "99") (name "unconnected-(U$5-PIN4-PadP4)") (class "Default")
      (node (ref "U$5") (pin "P4") (pinfunction "PIN4_P4") (pintype "bidirectional"))
    )
    (net (code "100") (name "unconnected-(U$15-IN1-Pad3)") (class "Default")
      (node (ref "U$15") (pin "3") (pinfunction "IN1_3") (pintype "bidirectional"))
    )
    (net (code "101") (name "unconnected-(U$15-IN2-Pad1)") (class "Default")
      (node (ref "U$15") (pin "1") (pinfunction "IN2_1") (pintype "bidirectional"))
    )
    (net (code "102") (name "unconnected-(U$15-IN3-Pad8)") (class "Default")
      (node (ref "U$15") (pin "8") (pinfunction "IN3_8") (pintype "bidirectional"))
    )
    (net (code "103") (name "unconnected-(U$15-IN4-Pad9)") (class "Default")
      (node (ref "U$15") (pin "9") (pinfunction "IN4_9") (pintype "bidirectional"))
    )
    (net (code "104") (name "unconnected-(U$15-IN8-Pad18)") (class "Default")
      (node (ref "U$15") (pin "18") (pinfunction "IN8_18") (pintype "bidirectional"))
    )
    (net (code "105") (name "unconnected-(U$15-OUT1-Pad4)") (class "Default")
      (node (ref "U$15") (pin "4") (pinfunction "OUT1_4") (pintype "bidirectional"))
    )
    (net (code "106") (name "unconnected-(U$15-OUT2-Pad5)") (class "Default")
      (node (ref "U$15") (pin "5") (pinfunction "OUT2_5") (pintype "bidirectional"))
    )
    (net (code "107") (name "unconnected-(U$15-OUT3-Pad6)") (class "Default")
      (node (ref "U$15") (pin "6") (pinfunction "OUT3_6") (pintype "bidirectional"))
    )
    (net (code "108") (name "unconnected-(U$15-OUT4-Pad7)") (class "Default")
      (node (ref "U$15") (pin "7") (pinfunction "OUT4_7") (pintype "bidirectional"))
    )
    (net (code "109") (name "unconnected-(U$15-OUT8-Pad17)") (class "Default")
      (node (ref "U$15") (pin "17") (pinfunction "OUT8_17") (pintype "bidirectional"))
    )
    (net (code "110") (name "unconnected-(X1-PadG2)") (class "Default")
      (node (ref "X1") (pin "G2") (pinfunction "G2_G2") (pintype "passive"))
    )
    (net (code "111") (name "unconnected-(X1B-F-Pad10)") (class "Default")
      (node (ref "X1") (pin "10") (pinfunction "F_10") (pintype "passive"))
    )
    (net (code "112") (name "unconnected-(X1C-F-Pad11)") (class "Default")
      (node (ref "X1") (pin "11") (pinfunction "F_11") (pintype "passive"))
    )
    (net (code "113") (name "unconnected-(X1D-F-Pad12)") (class "Default")
      (node (ref "X1") (pin "12") (pinfunction "F_12") (pintype "passive"))
    )
    (net (code "114") (name "unconnected-(X1H-F-Pad2)") (class "Default")
      (node (ref "X1") (pin "2") (pinfunction "F_2") (pintype "passive"))
    )
    (net (code "115") (name "unconnected-(X2-Pad1)") (class "Default")
      (node (ref "X2") (pin "1") (pinfunction "1_1") (pintype "passive"))
    )
    (net (code "116") (name "unconnected-(X2-Pad4)") (class "Default")
      (node (ref "X2") (pin "4") (pinfunction "4_4") (pintype "passive"))
    )
    (net (code "117") (name "unconnected-(X2-Pad6)") (class "Default")
      (node (ref "X2") (pin "6") (pinfunction "6_6") (pintype "passive"))
    )
    (net (code "118") (name "unconnected-(X2-Pad7)") (class "Default")
      (node (ref "X2") (pin "7") (pinfunction "7_7") (pintype "passive"))
    )
    (net (code "119") (name "unconnected-(X2-Pad8)") (class "Default")
      (node (ref "X2") (pin "8") (pinfunction "8_8") (pintype "passive"))
    )
    (net (code "120") (name "unconnected-(X2-Pad9)") (class "Default")
      (node (ref "X2") (pin "9") (pinfunction "9_9") (pintype "passive"))
    )
  )
)
